# MCP23017_I8O4_v1_0.net
KiCad netlist of a schematic drawn in EAGLE
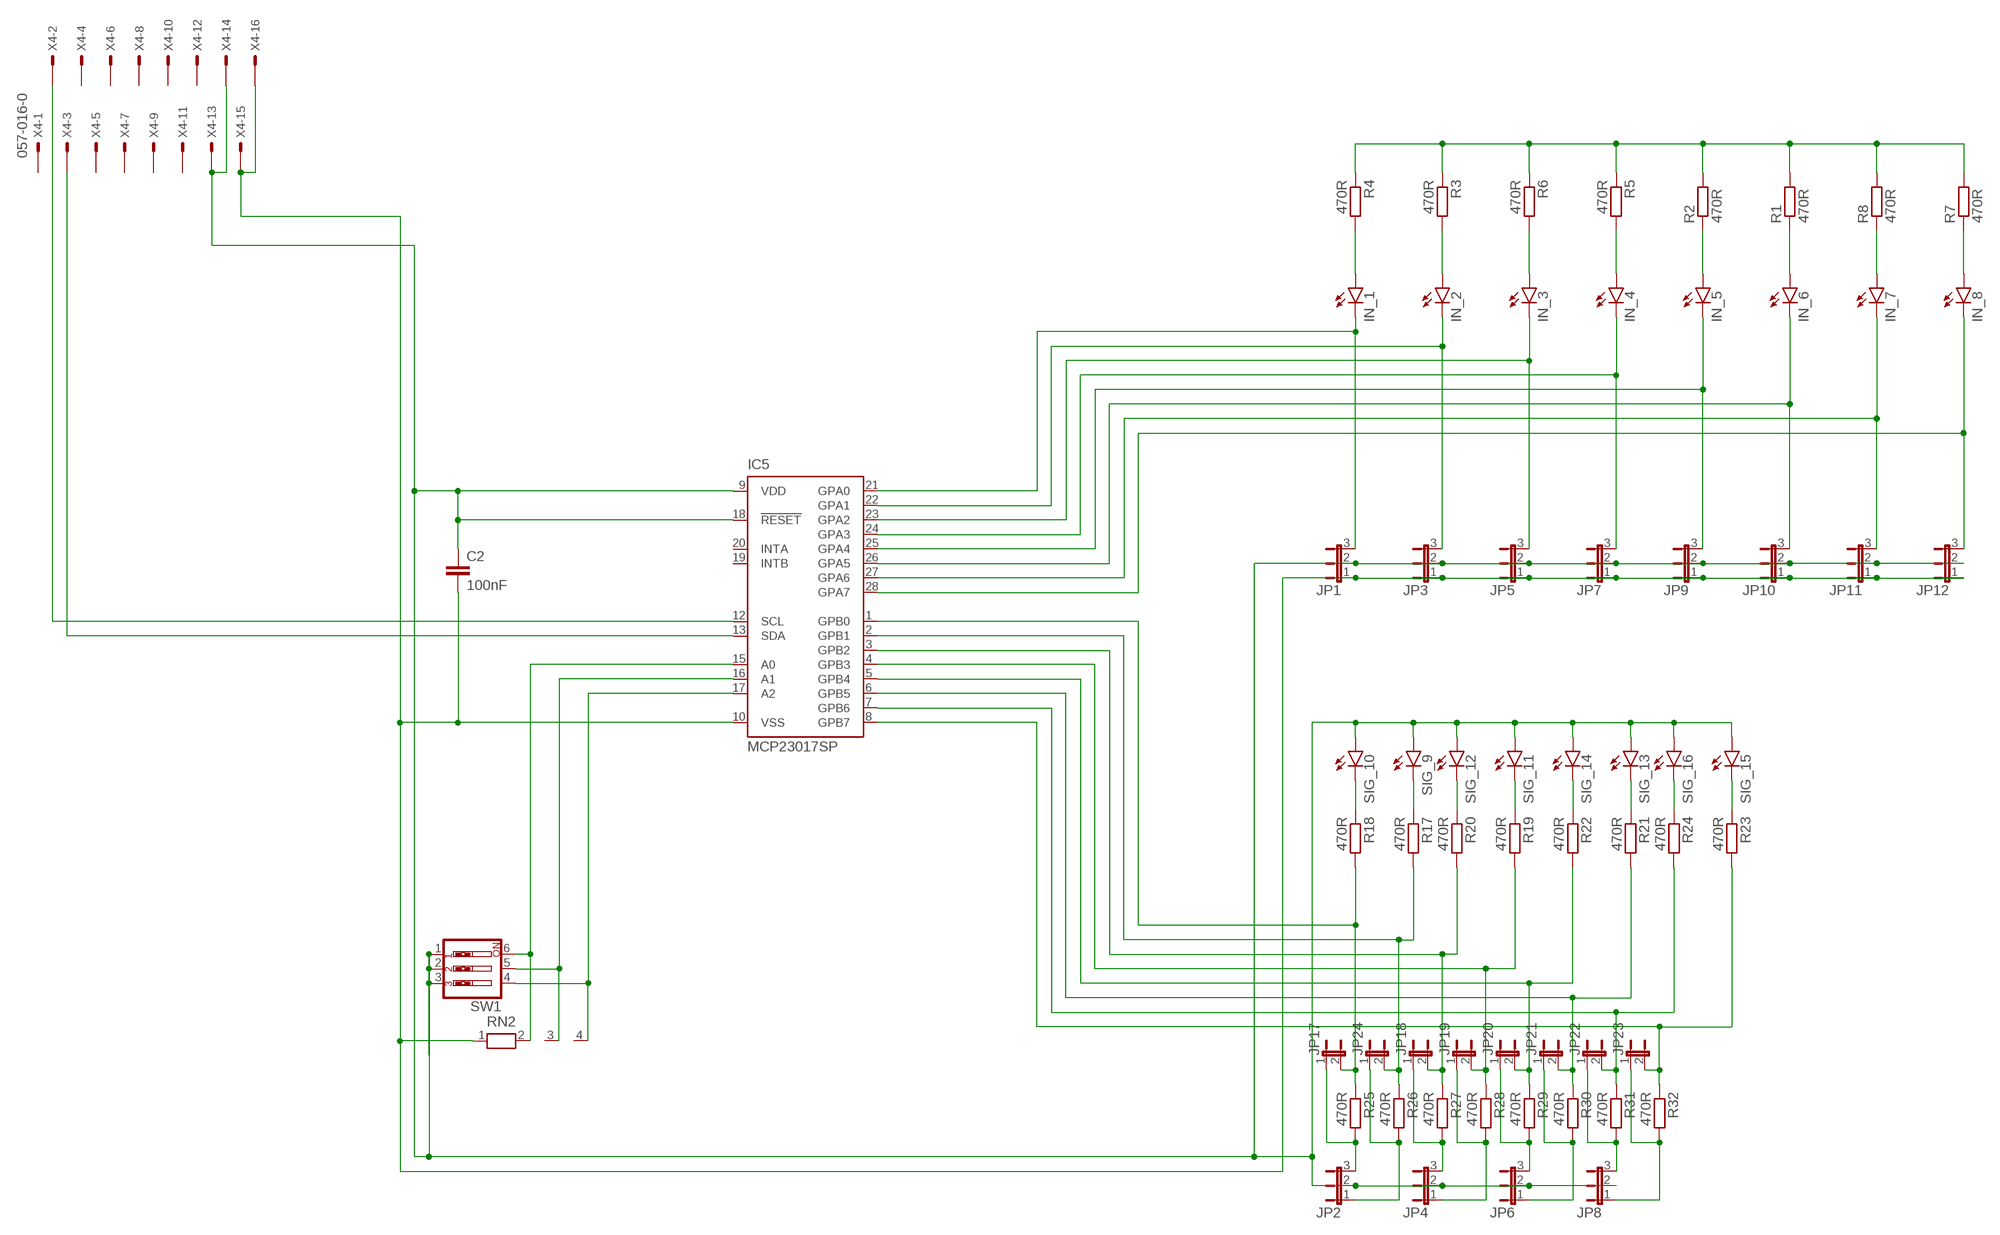
[diagram p0: schematic, sheet 1]

(export (version "E")
  (design (tool "Eeschema 10.0.6"))
  (components
    (comp (ref "C2")
      (value "100nF")
      (footprint "eagle-import:C025-024X044")
      (libsource (lib "eagle-import") (part "C-EU025-024X044"))
    )
    (comp (ref "IC5")
      (value "MCP23017SP")
      (footprint "eagle-import:DIL28-3")
      (libsource (lib "eagle-import") (part "MCP23017SP"))
    )
    (comp (ref "IN_1")
      (value "LED3MM")
      (footprint "eagle-import:LED3MM")
      (libsource (lib "eagle-import") (part "LED3MM"))
    )
    (comp (ref "IN_2")
      (value "LED3MM")
      (footprint "eagle-import:LED3MM")
      (libsource (lib "eagle-import") (part "LED3MM"))
    )
    (comp (ref "IN_3")
      (value "LED3MM")
      (footprint "eagle-import:LED3MM")
      (libsource (lib "eagle-import") (part "LED3MM"))
    )
    (comp (ref "IN_4")
      (value "LED3MM")
      (footprint "eagle-import:LED3MM")
      (libsource (lib "eagle-import") (part "LED3MM"))
    )
    (comp (ref "IN_5")
      (value "LED3MM")
      (footprint "eagle-import:LED3MM")
      (libsource (lib "eagle-import") (part "LED3MM"))
    )
    (comp (ref "IN_6")
      (value "LED3MM")
      (footprint "eagle-import:LED3MM")
      (libsource (lib "eagle-import") (part "LED3MM"))
    )
    (comp (ref "IN_7")
      (value "LED3MM")
      (footprint "eagle-import:LED3MM")
      (libsource (lib "eagle-import") (part "LED3MM"))
    )
    (comp (ref "IN_8")
      (value "LED3MM")
      (footprint "eagle-import:LED3MM")
      (libsource (lib "eagle-import") (part "LED3MM"))
    )
    (comp (ref "JP1")
      (value "JP2E")
      (footprint "eagle-import:JP2")
      (libsource (lib "eagle-import") (part "JP2E"))
    )
    (comp (ref "JP2")
      (value "JP2E")
      (footprint "eagle-import:JP2")
      (libsource (lib "eagle-import") (part "JP2E"))
    )
    (comp (ref "JP3")
      (value "JP2E")
      (footprint "eagle-import:JP2")
      (libsource (lib "eagle-import") (part "JP2E"))
    )
    (comp (ref "JP4")
      (value "JP2E")
      (footprint "eagle-import:JP2")
      (libsource (lib "eagle-import") (part "JP2E"))
    )
    (comp (ref "JP5")
      (value "JP2E")
      (footprint "eagle-import:JP2")
      (libsource (lib "eagle-import") (part "JP2E"))
    )
    (comp (ref "JP6")
      (value "JP2E")
      (footprint "eagle-import:JP2")
      (libsource (lib "eagle-import") (part "JP2E"))
    )
    (comp (ref "JP7")
      (value "JP2E")
      (footprint "eagle-import:JP2")
      (libsource (lib "eagle-import") (part "JP2E"))
    )
    (comp (ref "JP8")
      (value "JP2E")
      (footprint "eagle-import:JP2")
      (libsource (lib "eagle-import") (part "JP2E"))
    )
    (comp (ref "JP9")
      (value "JP2E")
      (footprint "eagle-import:JP2")
      (libsource (lib "eagle-import") (part "JP2E"))
    )
    (comp (ref "JP10")
      (value "JP2E")
      (footprint "eagle-import:JP2")
      (libsource (lib "eagle-import") (part "JP2E"))
    )
    (comp (ref "JP11")
      (value "JP2E")
      (footprint "eagle-import:JP2")
      (libsource (lib "eagle-import") (part "JP2E"))
    )
    (comp (ref "JP12")
      (value "JP2E")
      (footprint "eagle-import:JP2")
      (libsource (lib "eagle-import") (part "JP2E"))
    )
    (comp (ref "JP17")
      (value "JP1E")
      (footprint "eagle-import:JP1")
      (libsource (lib "eagle-import") (part "JP1E"))
    )
    (comp (ref "JP18")
      (value "JP1E")
      (footprint "eagle-import:JP1")
      (libsource (lib "eagle-import") (part "JP1E"))
    )
    (comp (ref "JP19")
      (value "JP1E")
      (footprint "eagle-import:JP1")
      (libsource (lib "eagle-import") (part "JP1E"))
    )
    (comp (ref "JP20")
      (value "JP1E")
      (footprint "eagle-import:JP1")
      (libsource (lib "eagle-import") (part "JP1E"))
    )
    (comp (ref "JP21")
      (value "JP1E")
      (footprint "eagle-import:JP1")
      (libsource (lib "eagle-import") (part "JP1E"))
    )
    (comp (ref "JP22")
      (value "JP1E")
      (footprint "eagle-import:JP1")
      (libsource (lib "eagle-import") (part "JP1E"))
    )
    (comp (ref "JP23")
      (value "JP1E")
      (footprint "eagle-import:JP1")
      (libsource (lib "eagle-import") (part "JP1E"))
    )
    (comp (ref "JP24")
      (value "JP1E")
      (footprint "eagle-import:JP1")
      (libsource (lib "eagle-import") (part "JP1E"))
    )
    (comp (ref "R1")
      (value "470R")
      (footprint "eagle-import:0309_10")
      (libsource (lib "eagle-import") (part "R-EU_0309/10"))
    )
    (comp (ref "R2")
      (value "470R")
      (footprint "eagle-import:0309_10")
      (libsource (lib "eagle-import") (part "R-EU_0309/10"))
    )
    (comp (ref "R3")
      (value "470R")
      (footprint "eagle-import:0309_10")
      (libsource (lib "eagle-import") (part "R-EU_0309/10"))
    )
    (comp (ref "R4")
      (value "470R")
      (footprint "eagle-import:0309_10")
      (libsource (lib "eagle-import") (part "R-EU_0309/10"))
    )
    (comp (ref "R5")
      (value "470R")
      (footprint "eagle-import:0309_10")
      (libsource (lib "eagle-import") (part "R-EU_0309/10"))
    )
    (comp (ref "R6")
      (value "470R")
      (footprint "eagle-import:0309_10")
      (libsource (lib "eagle-import") (part "R-EU_0309/10"))
    )
    (comp (ref "R7")
      (value "470R")
      (footprint "eagle-import:0309_10")
      (libsource (lib "eagle-import") (part "R-EU_0309/10"))
    )
    (comp (ref "R8")
      (value "470R")
      (footprint "eagle-import:0309_10")
      (libsource (lib "eagle-import") (part "R-EU_0309/10"))
    )
    (comp (ref "R17")
      (value "470R")
      (footprint "eagle-import:0309_10")
      (libsource (lib "eagle-import") (part "R-EU_0309/10"))
    )
    (comp (ref "R18")
      (value "470R")
      (footprint "eagle-import:0309_10")
      (libsource (lib "eagle-import") (part "R-EU_0309/10"))
    )
    (comp (ref "R19")
      (value "470R")
      (footprint "eagle-import:0309_10")
      (libsource (lib "eagle-import") (part "R-EU_0309/10"))
    )
    (comp (ref "R20")
      (value "470R")
      (footprint "eagle-import:0309_10")
      (libsource (lib "eagle-import") (part "R-EU_0309/10"))
    )
    (comp (ref "R21")
      (value "470R")
      (footprint "eagle-import:0309_10")
      (libsource (lib "eagle-import") (part "R-EU_0309/10"))
    )
    (comp (ref "R22")
      (value "470R")
      (footprint "eagle-import:0309_10")
      (libsource (lib "eagle-import") (part "R-EU_0309/10"))
    )
    (comp (ref "R23")
      (value "470R")
      (footprint "eagle-import:0309_10")
      (libsource (lib "eagle-import") (part "R-EU_0309/10"))
    )
    (comp (ref "R24")
      (value "470R")
      (footprint "eagle-import:0309_10")
      (libsource (lib "eagle-import") (part "R-EU_0309/10"))
    )
    (comp (ref "R25")
      (value "470R")
      (footprint "eagle-import:0309_10")
      (libsource (lib "eagle-import") (part "R-EU_0309/10"))
    )
    (comp (ref "R26")
      (value "470R")
      (footprint "eagle-import:0309_10")
      (libsource (lib "eagle-import") (part "R-EU_0309/10"))
    )
    (comp (ref "R27")
      (value "470R")
      (footprint "eagle-import:0309_10")
      (libsource (lib "eagle-import") (part "R-EU_0309/10"))
    )
    (comp (ref "R28")
      (value "470R")
      (footprint "eagle-import:0309_10")
      (libsource (lib "eagle-import") (part "R-EU_0309/10"))
    )
    (comp (ref "R29")
      (value "470R")
      (footprint "eagle-import:0309_10")
      (libsource (lib "eagle-import") (part "R-EU_0309/10"))
    )
    (comp (ref "R30")
      (value "470R")
      (footprint "eagle-import:0309_10")
      (libsource (lib "eagle-import") (part "R-EU_0309/10"))
    )
    (comp (ref "R31")
      (value "470R")
      (footprint "eagle-import:0309_10")
      (libsource (lib "eagle-import") (part "R-EU_0309/10"))
    )
    (comp (ref "R32")
      (value "470R")
      (footprint "eagle-import:0309_10")
      (libsource (lib "eagle-import") (part "R-EU_0309/10"))
    )
    (comp (ref "RN2")
      (value "RN03")
      (footprint "eagle-import:RN-3")
      (libsource (lib "eagle-import") (part "RN03"))
    )
    (comp (ref "SIG_9")
      (value "LED3MM")
      (footprint "eagle-import:LED3MM")
      (libsource (lib "eagle-import") (part "LED3MM"))
    )
    (comp (ref "SIG_10")
      (value "LED3MM")
      (footprint "eagle-import:LED3MM")
      (libsource (lib "eagle-import") (part "LED3MM"))
    )
    (comp (ref "SIG_11")
      (value "LED3MM")
      (footprint "eagle-import:LED3MM")
      (libsource (lib "eagle-import") (part "LED3MM"))
    )
    (comp (ref "SIG_12")
      (value "LED3MM")
      (footprint "eagle-import:LED3MM")
      (libsource (lib "eagle-import") (part "LED3MM"))
    )
    (comp (ref "SIG_13")
      (value "LED3MM")
      (footprint "eagle-import:LED3MM")
      (libsource (lib "eagle-import") (part "LED3MM"))
    )
    (comp (ref "SIG_14")
      (value "LED3MM")
      (footprint "eagle-import:LED3MM")
      (libsource (lib "eagle-import") (part "LED3MM"))
    )
    (comp (ref "SIG_15")
      (value "LED3MM")
      (footprint "eagle-import:LED3MM")
      (libsource (lib "eagle-import") (part "LED3MM"))
    )
    (comp (ref "SIG_16")
      (value "LED3MM")
      (footprint "eagle-import:LED3MM")
      (libsource (lib "eagle-import") (part "LED3MM"))
    )
    (comp (ref "SW1")
      (value "SW_DIP-3")
      (footprint "eagle-import:EDG-03")
      (libsource (lib "eagle-import") (part "SW_DIP-3"))
    )
    (comp (ref "X4")
      (value "057-016-0")
      (footprint "eagle-import:057-016-0")
      (libsource (lib "eagle-import") (part "057-016-0"))
    )
  )
  (nets
    (net (code "1") (name "Net-(IC5-A0)") (class "Default")
      (node (ref "IC5") (pin "15") (pinfunction "A0_15") (pintype "input"))
      (node (ref "RN2") (pin "2") (pinfunction "2_2") (pintype "passive"))
      (node (ref "SW1") (pin "6") (pinfunction "6_6") (pintype "passive"))
    )
    (net (code "2") (name "Net-(IC5-A1)") (class "Default")
      (node (ref "IC5") (pin "16") (pinfunction "A1_16") (pintype "input"))
      (node (ref "RN2") (pin "3") (pinfunction "3_3") (pintype "passive"))
      (node (ref "SW1") (pin "5") (pinfunction "5_5") (pintype "passive"))
    )
    (net (code "3") (name "Net-(IC5-A2)") (class "Default")
      (node (ref "IC5") (pin "17") (pinfunction "A2_17") (pintype "input"))
      (node (ref "RN2") (pin "4") (pinfunction "4_4") (pintype "passive"))
      (node (ref "SW1") (pin "4") (pinfunction "4_4") (pintype "passive"))
    )
    (net (code "4") (name "Net-(IC5-GPA0)") (class "Default")
      (node (ref "IC5") (pin "21") (pinfunction "GPA0_21") (pintype "bidirectional"))
      (node (ref "IN_1") (pin "K") (pinfunction "C_K") (pintype "passive"))
      (node (ref "JP1") (pin "3") (pinfunction "3_3") (pintype "passive"))
    )
    (net (code "5") (name "Net-(IC5-GPA1)") (class "Default")
      (node (ref "IC5") (pin "22") (pinfunction "GPA1_22") (pintype "bidirectional"))
      (node (ref "IN_2") (pin "K") (pinfunction "C_K") (pintype "passive"))
      (node (ref "JP3") (pin "3") (pinfunction "3_3") (pintype "passive"))
    )
    (net (code "6") (name "Net-(IC5-GPA2)") (class "Default")
      (node (ref "IC5") (pin "23") (pinfunction "GPA2_23") (pintype "bidirectional"))
      (node (ref "IN_3") (pin "K") (pinfunction "C_K") (pintype "passive"))
      (node (ref "JP5") (pin "3") (pinfunction "3_3") (pintype "passive"))
    )
    (net (code "7") (name "Net-(IC5-GPA3)") (class "Default")
      (node (ref "IC5") (pin "24") (pinfunction "GPA3_24") (pintype "bidirectional"))
      (node (ref "IN_4") (pin "K") (pinfunction "C_K") (pintype "passive"))
      (node (ref "JP7") (pin "3") (pinfunction "3_3") (pintype "passive"))
    )
    (net (code "8") (name "Net-(IC5-GPA4)") (class "Default")
      (node (ref "IC5") (pin "25") (pinfunction "GPA4_25") (pintype "bidirectional"))
      (node (ref "IN_5") (pin "K") (pinfunction "C_K") (pintype "passive"))
      (node (ref "JP9") (pin "3") (pinfunction "3_3") (pintype "passive"))
    )
    (net (code "9") (name "Net-(IC5-GPA5)") (class "Default")
      (node (ref "IC5") (pin "26") (pinfunction "GPA5_26") (pintype "bidirectional"))
      (node (ref "IN_6") (pin "K") (pinfunction "C_K") (pintype "passive"))
      (node (ref "JP10") (pin "3") (pinfunction "3_3") (pintype "passive"))
    )
    (net (code "10") (name "Net-(IC5-GPA6)") (class "Default")
      (node (ref "IC5") (pin "27") (pinfunction "GPA6_27") (pintype "bidirectional"))
      (node (ref "IN_7") (pin "K") (pinfunction "C_K") (pintype "passive"))
      (node (ref "JP11") (pin "3") (pinfunction "3_3") (pintype "passive"))
    )
    (net (code "11") (name "Net-(IC5-GPA7)") (class "Default")
      (node (ref "IC5") (pin "28") (pinfunction "GPA7_28") (pintype "bidirectional"))
      (node (ref "IN_8") (pin "K") (pinfunction "C_K") (pintype "passive"))
      (node (ref "JP12") (pin "3") (pinfunction "3_3") (pintype "passive"))
    )
    (net (code "12") (name "Net-(IC5-GPB0)") (class "Default")
      (node (ref "IC5") (pin "1") (pinfunction "GPB0_1") (pintype "bidirectional"))
      (node (ref "JP17") (pin "2") (pinfunction "2_2") (pintype "passive"))
      (node (ref "R18") (pin "2") (pinfunction "2_2") (pintype "passive"))
      (node (ref "R25") (pin "1") (pinfunction "1_1") (pintype "passive"))
    )
    (net (code "13") (name "Net-(IC5-GPB1)") (class "Default")
      (node (ref "IC5") (pin "2") (pinfunction "GPB1_2") (pintype "bidirectional"))
      (node (ref "JP24") (pin "2") (pinfunction "2_2") (pintype "passive"))
      (node (ref "R17") (pin "2") (pinfunction "2_2") (pintype "passive"))
      (node (ref "R26") (pin "1") (pinfunction "1_1") (pintype "passive"))
    )
    (net (code "14") (name "Net-(IC5-GPB2)") (class "Default")
      (node (ref "IC5") (pin "3") (pinfunction "GPB2_3") (pintype "bidirectional"))
      (node (ref "JP18") (pin "2") (pinfunction "2_2") (pintype "passive"))
      (node (ref "R20") (pin "2") (pinfunction "2_2") (pintype "passive"))
      (node (ref "R27") (pin "1") (pinfunction "1_1") (pintype "passive"))
    )
    (net (code "15") (name "Net-(IC5-GPB3)") (class "Default")
      (node (ref "IC5") (pin "4") (pinfunction "GPB3_4") (pintype "bidirectional"))
      (node (ref "JP19") (pin "2") (pinfunction "2_2") (pintype "passive"))
      (node (ref "R19") (pin "2") (pinfunction "2_2") (pintype "passive"))
      (node (ref "R28") (pin "1") (pinfunction "1_1") (pintype "passive"))
    )
    (net (code "16") (name "Net-(IC5-GPB4)") (class "Default")
      (node (ref "IC5") (pin "5") (pinfunction "GPB4_5") (pintype "bidirectional"))
      (node (ref "JP20") (pin "2") (pinfunction "2_2") (pintype "passive"))
      (node (ref "R22") (pin "2") (pinfunction "2_2") (pintype "passive"))
      (node (ref "R29") (pin "1") (pinfunction "1_1") (pintype "passive"))
    )
    (net (code "17") (name "Net-(IC5-GPB5)") (class "Default")
      (node (ref "IC5") (pin "6") (pinfunction "GPB5_6") (pintype "bidirectional"))
      (node (ref "JP21") (pin "2") (pinfunction "2_2") (pintype "passive"))
      (node (ref "R21") (pin "2") (pinfunction "2_2") (pintype "passive"))
      (node (ref "R30") (pin "1") (pinfunction "1_1") (pintype "passive"))
    )
    (net (code "18") (name "Net-(IC5-GPB6)") (class "Default")
      (node (ref "IC5") (pin "7") (pinfunction "GPB6_7") (pintype "bidirectional"))
      (node (ref "JP22") (pin "2") (pinfunction "2_2") (pintype "passive"))
      (node (ref "R24") (pin "2") (pinfunction "2_2") (pintype "passive"))
      (node (ref "R31") (pin "1") (pinfunction "1_1") (pintype "passive"))
    )
    (net (code "19") (name "Net-(IC5-GPB7)") (class "Default")
      (node (ref "IC5") (pin "8") (pinfunction "GPB7_8") (pintype "bidirectional"))
      (node (ref "JP23") (pin "2") (pinfunction "2_2") (pintype "passive"))
      (node (ref "R23") (pin "2") (pinfunction "2_2") (pintype "passive"))
      (node (ref "R32") (pin "1") (pinfunction "1_1") (pintype "passive"))
    )
    (net (code "20") (name "Net-(IC5-SCL)") (class "Default")
      (node (ref "IC5") (pin "12") (pinfunction "SCL_12") (pintype "input"))
      (node (ref "X4") (pin "2") (pinfunction "S_2") (pintype "passive"))
    )
    (net (code "21") (name "Net-(IC5-SDA)") (class "Default")
      (node (ref "IC5") (pin "13") (pinfunction "SDA_13") (pintype "bidirectional"))
      (node (ref "X4") (pin "3") (pinfunction "S_3") (pintype "passive"))
    )
    (net (code "22") (name "Net-(IC5-VDD)") (class "Default")
      (node (ref "C2") (pin "1") (pinfunction "1_1") (pintype "passive"))
      (node (ref "IC5") (pin "18") (pinfunction "~{RESET}_18") (pintype "input"))
      (node (ref "IC5") (pin "9") (pinfunction "VDD_9") (pintype "power_in"))
      (node (ref "JP1") (pin "2") (pinfunction "2_2") (pintype "passive"))
      (node (ref "JP10") (pin "2") (pinfunction "2_2") (pintype "passive"))
      (node (ref "JP11") (pin "2") (pinfunction "2_2") (pintype "passive"))
      (node (ref "JP12") (pin "2") (pinfunction "2_2") (pintype "passive"))
      (node (ref "JP2") (pin "2") (pinfunction "2_2") (pintype "passive"))
      (node (ref "JP3") (pin "2") (pinfunction "2_2") (pintype "passive"))
      (node (ref "JP4") (pin "2") (pinfunction "2_2") (pintype "passive"))
      (node (ref "JP5") (pin "2") (pinfunction "2_2") (pintype "passive"))
      (node (ref "JP6") (pin "2") (pinfunction "2_2") (pintype "passive"))
      (node (ref "JP7") (pin "2") (pinfunction "2_2") (pintype "passive"))
      (node (ref "JP8") (pin "2") (pinfunction "2_2") (pintype "passive"))
      (node (ref "JP9") (pin "2") (pinfunction "2_2") (pintype "passive"))
      (node (ref "SIG_10") (pin "A") (pinfunction "A_A") (pintype "passive"))
      (node (ref "SIG_11") (pin "A") (pinfunction "A_A") (pintype "passive"))
      (node (ref "SIG_12") (pin "A") (pinfunction "A_A") (pintype "passive"))
      (node (ref "SIG_13") (pin "A") (pinfunction "A_A") (pintype "passive"))
      (node (ref "SIG_14") (pin "A") (pinfunction "A_A") (pintype "passive"))
      (node (ref "SIG_15") (pin "A") (pinfunction "A_A") (pintype "passive"))
      (node (ref "SIG_16") (pin "A") (pinfunction "A_A") (pintype "passive"))
      (node (ref "SIG_9") (pin "A") (pinfunction "A_A") (pintype "passive"))
      (node (ref "SW1") (pin "1") (pinfunction "1_1") (pintype "passive"))
      (node (ref "SW1") (pin "2") (pinfunction "2_2") (pintype "passive"))
      (node (ref "SW1") (pin "3") (pinfunction "3_3") (pintype "passive"))
      (node (ref "X4") (pin "13") (pinfunction "S_13") (pintype "passive"))
      (node (ref "X4") (pin "14") (pinfunction "S_14") (pintype "passive"))
    )
    (net (code "23") (name "Net-(IC5-VSS)") (class "Default")
      (node (ref "C2") (pin "2") (pinfunction "2_2") (pintype "passive"))
      (node (ref "IC5") (pin "10") (pinfunction "VSS_10") (pintype "power_in"))
      (node (ref "JP1") (pin "1") (pinfunction "1_1") (pintype "passive"))
      (node (ref "JP10") (pin "1") (pinfunction "1_1") (pintype "passive"))
      (node (ref "JP11") (pin "1") (pinfunction "1_1") (pintype "passive"))
      (node (ref "JP12") (pin "1") (pinfunction "1_1") (pintype "passive"))
      (node (ref "JP3") (pin "1") (pinfunction "1_1") (pintype "passive"))
      (node (ref "JP5") (pin "1") (pinfunction "1_1") (pintype "passive"))
      (node (ref "JP7") (pin "1") (pinfunction "1_1") (pintype "passive"))
      (node (ref "JP9") (pin "1") (pinfunction "1_1") (pintype "passive"))
      (node (ref "RN2") (pin "1") (pinfunction "1_1") (pintype "passive"))
      (node (ref "X4") (pin "15") (pinfunction "S_15") (pintype "passive"))
      (node (ref "X4") (pin "16") (pinfunction "S_16") (pintype "passive"))
    )
    (net (code "24") (name "Net-(IN_1-PadA)") (class "Default")
      (node (ref "IN_1") (pin "A") (pinfunction "A_A") (pintype "passive"))
      (node (ref "R4") (pin "2") (pinfunction "2_2") (pintype "passive"))
    )
    (net (code "25") (name "Net-(IN_2-PadA)") (class "Default")
      (node (ref "IN_2") (pin "A") (pinfunction "A_A") (pintype "passive"))
      (node (ref "R3") (pin "2") (pinfunction "2_2") (pintype "passive"))
    )
    (net (code "26") (name "Net-(IN_3-PadA)") (class "Default")
      (node (ref "IN_3") (pin "A") (pinfunction "A_A") (pintype "passive"))
      (node (ref "R6") (pin "2") (pinfunction "2_2") (pintype "passive"))
    )
    (net (code "27") (name "Net-(IN_4-PadA)") (class "Default")
      (node (ref "IN_4") (pin "A") (pinfunction "A_A") (pintype "passive"))
      (node (ref "R5") (pin "2") (pinfunction "2_2") (pintype "passive"))
    )
    (net (code "28") (name "Net-(IN_5-PadA)") (class "Default")
      (node (ref "IN_5") (pin "A") (pinfunction "A_A") (pintype "passive"))
      (node (ref "R2") (pin "1") (pinfunction "1_1") (pintype "passive"))
    )
    (net (code "29") (name "Net-(IN_6-PadA)") (class "Default")
      (node (ref "IN_6") (pin "A") (pinfunction "A_A") (pintype "passive"))
      (node (ref "R1") (pin "1") (pinfunction "1_1") (pintype "passive"))
    )
    (net (code "30") (name "Net-(IN_7-PadA)") (class "Default")
      (node (ref "IN_7") (pin "A") (pinfunction "A_A") (pintype "passive"))
      (node (ref "R8") (pin "1") (pinfunction "1_1") (pintype "passive"))
    )
    (net (code "31") (name "Net-(IN_8-PadA)") (class "Default")
      (node (ref "IN_8") (pin "A") (pinfunction "A_A") (pintype "passive"))
      (node (ref "R7") (pin "1") (pinfunction "1_1") (pintype "passive"))
    )
    (net (code "32") (name "Net-(JP2-Pad1)") (class "Default")
      (node (ref "JP2") (pin "1") (pinfunction "1_1") (pintype "passive"))
      (node (ref "JP24") (pin "1") (pinfunction "1_1") (pintype "passive"))
      (node (ref "R26") (pin "2") (pinfunction "2_2") (pintype "passive"))
    )
    (net (code "33") (name "Net-(JP17-Pad1)") (class "Default")
      (node (ref "JP17") (pin "1") (pinfunction "1_1") (pintype "passive"))
      (node (ref "JP2") (pin "3") (pinfunction "3_3") (pintype "passive"))
      (node (ref "R25") (pin "2") (pinfunction "2_2") (pintype "passive"))
    )
    (net (code "34") (name "Net-(JP18-Pad1)") (class "Default")
      (node (ref "JP18") (pin "1") (pinfunction "1_1") (pintype "passive"))
      (node (ref "JP4") (pin "3") (pinfunction "3_3") (pintype "passive"))
      (node (ref "R27") (pin "2") (pinfunction "2_2") (pintype "passive"))
    )
    (net (code "35") (name "Net-(JP19-Pad1)") (class "Default")
      (node (ref "JP19") (pin "1") (pinfunction "1_1") (pintype "passive"))
      (node (ref "JP4") (pin "1") (pinfunction "1_1") (pintype "passive"))
      (node (ref "R28") (pin "2") (pinfunction "2_2") (pintype "passive"))
    )
    (net (code "36") (name "Net-(JP20-Pad1)") (class "Default")
      (node (ref "JP20") (pin "1") (pinfunction "1_1") (pintype "passive"))
      (node (ref "JP6") (pin "3") (pinfunction "3_3") (pintype "passive"))
      (node (ref "R29") (pin "2") (pinfunction "2_2") (pintype "passive"))
    )
    (net (code "37") (name "Net-(JP21-Pad1)") (class "Default")
      (node (ref "JP21") (pin "1") (pinfunction "1_1") (pintype "passive"))
      (node (ref "JP6") (pin "1") (pinfunction "1_1") (pintype "passive"))
      (node (ref "R30") (pin "2") (pinfunction "2_2") (pintype "passive"))
    )
    (net (code "38") (name "Net-(JP22-Pad1)") (class "Default")
      (node (ref "JP22") (pin "1") (pinfunction "1_1") (pintype "passive"))
      (node (ref "JP8") (pin "3") (pinfunction "3_3") (pintype "passive"))
      (node (ref "R31") (pin "2") (pinfunction "2_2") (pintype "passive"))
    )
    (net (code "39") (name "Net-(JP23-Pad1)") (class "Default")
      (node (ref "JP23") (pin "1") (pinfunction "1_1") (pintype "passive"))
      (node (ref "JP8") (pin "1") (pinfunction "1_1") (pintype "passive"))
      (node (ref "R32") (pin "2") (pinfunction "2_2") (pintype "passive"))
    )
    (net (code "40") (name "Net-(R1-Pad2)") (class "Default")
      (node (ref "R1") (pin "2") (pinfunction "2_2") (pintype "passive"))
      (node (ref "R2") (pin "2") (pinfunction "2_2") (pintype "passive"))
      (node (ref "R3") (pin "1") (pinfunction "1_1") (pintype "passive"))
      (node (ref "R4") (pin "1") (pinfunction "1_1") (pintype "passive"))
      (node (ref "R5") (pin "1") (pinfunction "1_1") (pintype "passive"))
      (node (ref "R6") (pin "1") (pinfunction "1_1") (pintype "passive"))
      (node (ref "R7") (pin "2") (pinfunction "2_2") (pintype "passive"))
      (node (ref "R8") (pin "2") (pinfunction "2_2") (pintype "passive"))
    )
    (net (code "41") (name "Net-(SIG_9-C)") (class "Default")
      (node (ref "R17") (pin "1") (pinfunction "1_1") (pintype "passive"))
      (node (ref "SIG_9") (pin "K") (pinfunction "C_K") (pintype "passive"))
    )
    (net (code "42") (name "Net-(SIG_10-C)") (class "Default")
      (node (ref "R18") (pin "1") (pinfunction "1_1") (pintype "passive"))
      (node (ref "SIG_10") (pin "K") (pinfunction "C_K") (pintype "passive"))
    )
    (net (code "43") (name "Net-(SIG_11-C)") (class "Default")
      (node (ref "R19") (pin "1") (pinfunction "1_1") (pintype "passive"))
      (node (ref "SIG_11") (pin "K") (pinfunction "C_K") (pintype "passive"))
    )
    (net (code "44") (name "Net-(SIG_12-C)") (class "Default")
      (node (ref "R20") (pin "1") (pinfunction "1_1") (pintype "passive"))
      (node (ref "SIG_12") (pin "K") (pinfunction "C_K") (pintype "passive"))
    )
    (net (code "45") (name "Net-(SIG_13-C)") (class "Default")
      (node (ref "R21") (pin "1") (pinfunction "1_1") (pintype "passive"))
      (node (ref "SIG_13") (pin "K") (pinfunction "C_K") (pintype "passive"))
    )
    (net (code "46") (name "Net-(SIG_14-C)") (class "Default")
      (node (ref "R22") (pin "1") (pinfunction "1_1") (pintype "passive"))
      (node (ref "SIG_14") (pin "K") (pinfunction "C_K") (pintype "passive"))
    )
    (net (code "47") (name "Net-(SIG_15-C)") (class "Default")
      (node (ref "R23") (pin "1") (pinfunction "1_1") (pintype "passive"))
      (node (ref "SIG_15") (pin "K") (pinfunction "C_K") (pintype "passive"))
    )
    (net (code "48") (name "Net-(SIG_16-C)") (class "Default")
      (node (ref "R24") (pin "1") (pinfunction "1_1") (pintype "passive"))
      (node (ref "SIG_16") (pin "K") (pinfunction "C_K") (pintype "passive"))
    )
    (net (code "49") (name "unconnected-(IC5-INTA-Pad20)") (class "Default")
      (node (ref "IC5") (pin "20") (pinfunction "INTA_20") (pintype "output"))
    )
    (net (code "50") (name "unconnected-(IC5-INTB-Pad19)") (class "Default")
      (node (ref "IC5") (pin "19") (pinfunction "INTB_19") (pintype "output"))
    )
    (net (code "51") (name "unconnected-(X4A-S-Pad1)") (class "Default")
      (node (ref "X4") (pin "1") (pinfunction "S_1") (pintype "passive"))
    )
    (net (code "52") (name "unconnected-(X4B-S-Pad10)") (class "Default")
      (node (ref "X4") (pin "10") (pinfunction "S_10") (pintype "passive"))
    )
    (net (code "53") (name "unconnected-(X4C-S-Pad11)") (class "Default")
      (node (ref "X4") (pin "11") (pinfunction "S_11") (pintype "passive"))
    )
    (net (code "54") (name "unconnected-(X4D-S-Pad12)") (class "Default")
      (node (ref "X4") (pin "12") (pinfunction "S_12") (pintype "passive"))
    )
    (net (code "55") (name "unconnected-(X4K-S-Pad4)") (class "Default")
      (node (ref "X4") (pin "4") (pinfunction "S_4") (pintype "passive"))
    )
    (net (code "56") (name "unconnected-(X4L-S-Pad5)") (class "Default")
      (node (ref "X4") (pin "5") (pinfunction "S_5") (pintype "passive"))
    )
    (net (code "57") (name "unconnected-(X4M-S-Pad6)") (class "Default")
      (node (ref "X4") (pin "6") (pinfunction "S_6") (pintype "passive"))
    )
    (net (code "58") (name "unconnected-(X4N-S-Pad7)") (class "Default")
      (node (ref "X4") (pin "7") (pinfunction "S_7") (pintype "passive"))
    )
    (net (code "59") (name "unconnected-(X4O-S-Pad8)") (class "Default")
      (node (ref "X4") (pin "8") (pinfunction "S_8") (pintype "passive"))
    )
    (net (code "60") (name "unconnected-(X4P-S-Pad9)") (class "Default")
      (node (ref "X4") (pin "9") (pinfunction "S_9") (pintype "passive"))
    )
  )
)
